# TMS320F28379D_TRIP.net
KiCad netlist of a schematic drawn in Altium Designer
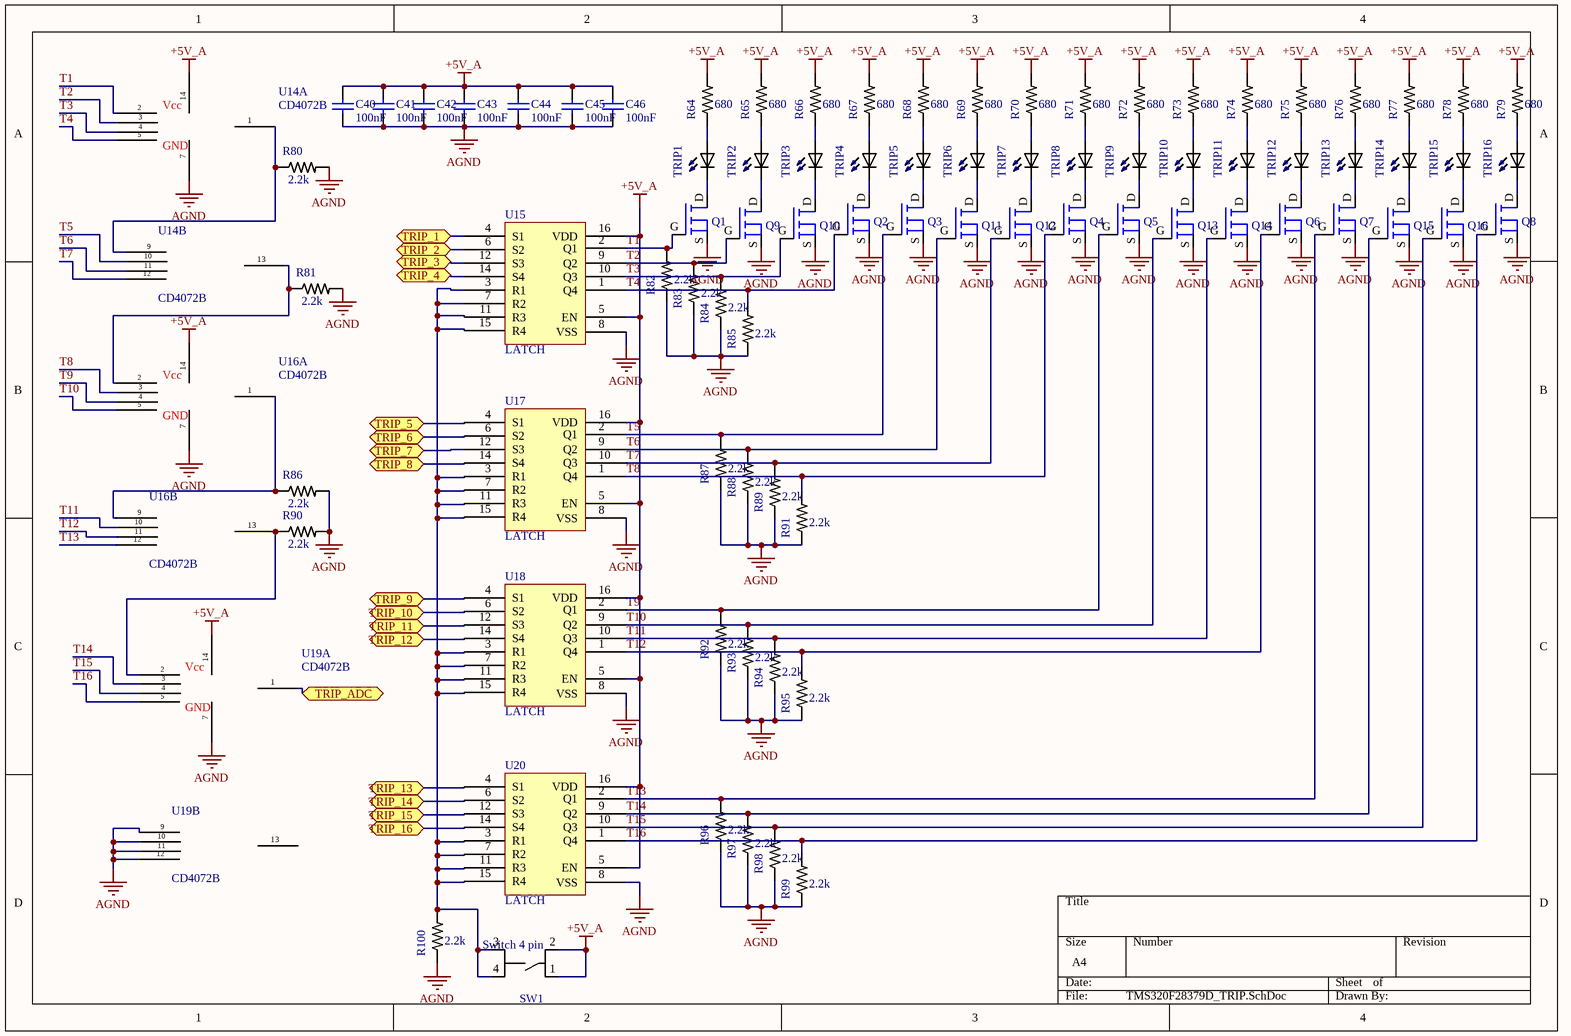
[diagram p0: TMS320F28379D_TRIP.SchDoc]

(export (version "E")
  (design (tool "Eeschema 10.0.6"))
  (components
    (comp (ref "C40")
      (value "100nF")
      (footprint "CAP 0805")
      (fields (field (name "Comment") "Cap cerámico"))
      (libsource (lib "Condensadores") (part "Cap cerámico"))
    )
    (comp (ref "C41")
      (value "100nF")
      (footprint "CAP 0805")
      (fields (field (name "Comment") "Cap cerámico"))
      (libsource (lib "Condensadores") (part "Cap cerámico"))
    )
    (comp (ref "C42")
      (value "100nF")
      (footprint "CAP 0805")
      (fields (field (name "Comment") "Cap cerámico"))
      (libsource (lib "Condensadores") (part "Cap cerámico"))
    )
    (comp (ref "C43")
      (value "100nF")
      (footprint "CAP 0805")
      (fields (field (name "Comment") "Cap cerámico"))
      (libsource (lib "Condensadores") (part "Cap cerámico"))
    )
    (comp (ref "C44")
      (value "100nF")
      (footprint "CAP 0805")
      (fields (field (name "Comment") "Cap cerámico"))
      (libsource (lib "Condensadores") (part "Cap cerámico"))
    )
    (comp (ref "C45")
      (value "100nF")
      (footprint "CAP 0805")
      (fields (field (name "Comment") "Cap cerámico"))
      (libsource (lib "Condensadores") (part "Cap cerámico"))
    )
    (comp (ref "C46")
      (value "100nF")
      (footprint "CAP 0805")
      (fields (field (name "Comment") "Cap cerámico"))
      (libsource (lib "Condensadores") (part "Cap cerámico"))
    )
    (comp (ref "Q1")
      (value "MOSFET N")
      (footprint "SOT23")
      (description "2N7002-FDICT-ND")
      (fields (field (name "MANUFACTURER PART NUMBER") "2N7002-7-F"))
      (libsource (lib "Power Semiconductors") (part "MOSFET_N"))
    )
    (comp (ref "Q2")
      (value "MOSFET N")
      (footprint "SOT23")
      (description "2N7002-FDICT-ND")
      (fields (field (name "MANUFACTURER PART NUMBER") "2N7002-7-F"))
      (libsource (lib "Power Semiconductors") (part "MOSFET_N"))
    )
    (comp (ref "Q3")
      (value "MOSFET N")
      (footprint "SOT23")
      (description "2N7002-FDICT-ND")
      (fields (field (name "MANUFACTURER PART NUMBER") "2N7002-7-F"))
      (libsource (lib "Power Semiconductors") (part "MOSFET_N"))
    )
    (comp (ref "Q4")
      (value "MOSFET N")
      (footprint "SOT23")
      (description "2N7002-FDICT-ND")
      (fields (field (name "MANUFACTURER PART NUMBER") "2N7002-7-F"))
      (libsource (lib "Power Semiconductors") (part "MOSFET_N"))
    )
    (comp (ref "Q5")
      (value "MOSFET N")
      (footprint "SOT23")
      (description "2N7002-FDICT-ND")
      (fields (field (name "MANUFACTURER PART NUMBER") "2N7002-7-F"))
      (libsource (lib "Power Semiconductors") (part "MOSFET_N"))
    )
    (comp (ref "Q6")
      (value "MOSFET N")
      (footprint "SOT23")
      (description "2N7002-FDICT-ND")
      (fields (field (name "MANUFACTURER PART NUMBER") "2N7002-7-F"))
      (libsource (lib "Power Semiconductors") (part "MOSFET_N"))
    )
    (comp (ref "Q7")
      (value "MOSFET N")
      (footprint "SOT23")
      (description "2N7002-FDICT-ND")
      (fields (field (name "MANUFACTURER PART NUMBER") "2N7002-7-F"))
      (libsource (lib "Power Semiconductors") (part "MOSFET_N"))
    )
    (comp (ref "Q8")
      (value "MOSFET N")
      (footprint "SOT23")
      (description "2N7002-FDICT-ND")
      (fields (field (name "MANUFACTURER PART NUMBER") "2N7002-7-F"))
      (libsource (lib "Power Semiconductors") (part "MOSFET_N"))
    )
    (comp (ref "Q9")
      (value "MOSFET N")
      (footprint "SOT23")
      (description "2N7002-FDICT-ND")
      (fields (field (name "MANUFACTURER PART NUMBER") "2N7002-7-F"))
      (libsource (lib "Power Semiconductors") (part "MOSFET_N"))
    )
    (comp (ref "Q10")
      (value "MOSFET N")
      (footprint "SOT23")
      (description "2N7002-FDICT-ND")
      (fields (field (name "MANUFACTURER PART NUMBER") "2N7002-7-F"))
      (libsource (lib "Power Semiconductors") (part "MOSFET_N"))
    )
    (comp (ref "Q11")
      (value "MOSFET N")
      (footprint "SOT23")
      (description "2N7002-FDICT-ND")
      (fields (field (name "MANUFACTURER PART NUMBER") "2N7002-7-F"))
      (libsource (lib "Power Semiconductors") (part "MOSFET_N"))
    )
    (comp (ref "Q12")
      (value "MOSFET N")
      (footprint "SOT23")
      (description "2N7002-FDICT-ND")
      (fields (field (name "MANUFACTURER PART NUMBER") "2N7002-7-F"))
      (libsource (lib "Power Semiconductors") (part "MOSFET_N"))
    )
    (comp (ref "Q13")
      (value "MOSFET N")
      (footprint "SOT23")
      (description "2N7002-FDICT-ND")
      (fields (field (name "MANUFACTURER PART NUMBER") "2N7002-7-F"))
      (libsource (lib "Power Semiconductors") (part "MOSFET_N"))
    )
    (comp (ref "Q14")
      (value "MOSFET N")
      (footprint "SOT23")
      (description "2N7002-FDICT-ND")
      (fields (field (name "MANUFACTURER PART NUMBER") "2N7002-7-F"))
      (libsource (lib "Power Semiconductors") (part "MOSFET_N"))
    )
    (comp (ref "Q15")
      (value "MOSFET N")
      (footprint "SOT23")
      (description "2N7002-FDICT-ND")
      (fields (field (name "MANUFACTURER PART NUMBER") "2N7002-7-F"))
      (libsource (lib "Power Semiconductors") (part "MOSFET_N"))
    )
    (comp (ref "Q16")
      (value "MOSFET N")
      (footprint "SOT23")
      (description "2N7002-FDICT-ND")
      (fields (field (name "MANUFACTURER PART NUMBER") "2N7002-7-F"))
      (libsource (lib "Power Semiconductors") (part "MOSFET_N"))
    )
    (comp (ref "R64")
      (value "680")
      (footprint "Resistor 0805")
      (description "Resistor")
      (fields (field (name "Comment") "Resistor 0805"))
      (libsource (lib "Resistencias") (part "Resistor"))
    )
    (comp (ref "R65")
      (value "680")
      (footprint "Resistor 0805")
      (description "Resistor")
      (fields (field (name "Comment") "Resistor 0805"))
      (libsource (lib "Resistencias") (part "Resistor"))
    )
    (comp (ref "R66")
      (value "680")
      (footprint "Resistor 0805")
      (description "Resistor")
      (fields (field (name "Comment") "Resistor 0805"))
      (libsource (lib "Resistencias") (part "Resistor"))
    )
    (comp (ref "R67")
      (value "680")
      (footprint "Resistor 0805")
      (description "Resistor")
      (fields (field (name "Comment") "Resistor 0805"))
      (libsource (lib "Resistencias") (part "Resistor"))
    )
    (comp (ref "R68")
      (value "680")
      (footprint "Resistor 0805")
      (description "Resistor")
      (fields (field (name "Comment") "Resistor 0805"))
      (libsource (lib "Resistencias") (part "Resistor"))
    )
    (comp (ref "R69")
      (value "680")
      (footprint "Resistor 0805")
      (description "Resistor")
      (fields (field (name "Comment") "Resistor 0805"))
      (libsource (lib "Resistencias") (part "Resistor"))
    )
    (comp (ref "R70")
      (value "680")
      (footprint "Resistor 0805")
      (description "Resistor")
      (fields (field (name "Comment") "Resistor 0805"))
      (libsource (lib "Resistencias") (part "Resistor"))
    )
    (comp (ref "R71")
      (value "680")
      (footprint "Resistor 0805")
      (description "Resistor")
      (fields (field (name "Comment") "Resistor 0805"))
      (libsource (lib "Resistencias") (part "Resistor"))
    )
    (comp (ref "R72")
      (value "680")
      (footprint "Resistor 0805")
      (description "Resistor")
      (fields (field (name "Comment") "Resistor 0805"))
      (libsource (lib "Resistencias") (part "Resistor"))
    )
    (comp (ref "R73")
      (value "680")
      (footprint "Resistor 0805")
      (description "Resistor")
      (fields (field (name "Comment") "Resistor 0805"))
      (libsource (lib "Resistencias") (part "Resistor"))
    )
    (comp (ref "R74")
      (value "680")
      (footprint "Resistor 0805")
      (description "Resistor")
      (fields (field (name "Comment") "Resistor 0805"))
      (libsource (lib "Resistencias") (part "Resistor"))
    )
    (comp (ref "R75")
      (value "680")
      (footprint "Resistor 0805")
      (description "Resistor")
      (fields (field (name "Comment") "Resistor 0805"))
      (libsource (lib "Resistencias") (part "Resistor"))
    )
    (comp (ref "R76")
      (value "680")
      (footprint "Resistor 0805")
      (description "Resistor")
      (fields (field (name "Comment") "Resistor 0805"))
      (libsource (lib "Resistencias") (part "Resistor"))
    )
    (comp (ref "R77")
      (value "680")
      (footprint "Resistor 0805")
      (description "Resistor")
      (fields (field (name "Comment") "Resistor 0805"))
      (libsource (lib "Resistencias") (part "Resistor"))
    )
    (comp (ref "R78")
      (value "680")
      (footprint "Resistor 0805")
      (description "Resistor")
      (fields (field (name "Comment") "Resistor 0805"))
      (libsource (lib "Resistencias") (part "Resistor"))
    )
    (comp (ref "R79")
      (value "680")
      (footprint "Resistor 0805")
      (description "Resistor")
      (fields (field (name "Comment") "Resistor 0805"))
      (libsource (lib "Resistencias") (part "Resistor"))
    )
    (comp (ref "R80")
      (value "2.2k")
      (footprint "Resistor 0805")
      (description "Resistor")
      (fields (field (name "Comment") "Resistor 0805"))
      (libsource (lib "Resistencias") (part "Resistor"))
    )
    (comp (ref "R81")
      (value "2.2k")
      (footprint "Resistor 0805")
      (description "Resistor")
      (fields (field (name "Comment") "Resistor 0805"))
      (libsource (lib "Resistencias") (part "Resistor"))
    )
    (comp (ref "R82")
      (value "2.2k")
      (footprint "Resistor 0805")
      (description "Resistor")
      (fields (field (name "Comment") "Resistor 0805"))
      (libsource (lib "Resistencias") (part "Resistor"))
    )
    (comp (ref "R83")
      (value "2.2k")
      (footprint "Resistor 0805")
      (description "Resistor")
      (fields (field (name "Comment") "Resistor 0805"))
      (libsource (lib "Resistencias") (part "Resistor"))
    )
    (comp (ref "R84")
      (value "2.2k")
      (footprint "Resistor 0805")
      (description "Resistor")
      (fields (field (name "Comment") "Resistor 0805"))
      (libsource (lib "Resistencias") (part "Resistor"))
    )
    (comp (ref "R85")
      (value "2.2k")
      (footprint "Resistor 0805")
      (description "Resistor")
      (fields (field (name "Comment") "Resistor 0805"))
      (libsource (lib "Resistencias") (part "Resistor"))
    )
    (comp (ref "R86")
      (value "2.2k")
      (footprint "Resistor 0805")
      (description "Resistor")
      (fields (field (name "Comment") "Resistor 0805"))
      (libsource (lib "Resistencias") (part "Resistor"))
    )
    (comp (ref "R87")
      (value "2.2k")
      (footprint "Resistor 0805")
      (description "Resistor")
      (fields (field (name "Comment") "Resistor 0805"))
      (libsource (lib "Resistencias") (part "Resistor"))
    )
    (comp (ref "R88")
      (value "2.2k")
      (footprint "Resistor 0805")
      (description "Resistor")
      (fields (field (name "Comment") "Resistor 0805"))
      (libsource (lib "Resistencias") (part "Resistor"))
    )
    (comp (ref "R89")
      (value "2.2k")
      (footprint "Resistor 0805")
      (description "Resistor")
      (fields (field (name "Comment") "Resistor 0805"))
      (libsource (lib "Resistencias") (part "Resistor"))
    )
    (comp (ref "R90")
      (value "2.2k")
      (footprint "Resistor 0805")
      (description "Resistor")
      (fields (field (name "Comment") "Resistor 0805"))
      (libsource (lib "Resistencias") (part "Resistor"))
    )
    (comp (ref "R91")
      (value "2.2k")
      (footprint "Resistor 0805")
      (description "Resistor")
      (fields (field (name "Comment") "Resistor 0805"))
      (libsource (lib "Resistencias") (part "Resistor"))
    )
    (comp (ref "R92")
      (value "2.2k")
      (footprint "Resistor 0805")
      (description "Resistor")
      (fields (field (name "Comment") "Resistor 0805"))
      (libsource (lib "Resistencias") (part "Resistor"))
    )
    (comp (ref "R93")
      (value "2.2k")
      (footprint "Resistor 0805")
      (description "Resistor")
      (fields (field (name "Comment") "Resistor 0805"))
      (libsource (lib "Resistencias") (part "Resistor"))
    )
    (comp (ref "R94")
      (value "2.2k")
      (footprint "Resistor 0805")
      (description "Resistor")
      (fields (field (name "Comment") "Resistor 0805"))
      (libsource (lib "Resistencias") (part "Resistor"))
    )
    (comp (ref "R95")
      (value "2.2k")
      (footprint "Resistor 0805")
      (description "Resistor")
      (fields (field (name "Comment") "Resistor 0805"))
      (libsource (lib "Resistencias") (part "Resistor"))
    )
    (comp (ref "R96")
      (value "2.2k")
      (footprint "Resistor 0805")
      (description "Resistor")
      (fields (field (name "Comment") "Resistor 0805"))
      (libsource (lib "Resistencias") (part "Resistor"))
    )
    (comp (ref "R97")
      (value "2.2k")
      (footprint "Resistor 0805")
      (description "Resistor")
      (fields (field (name "Comment") "Resistor 0805"))
      (libsource (lib "Resistencias") (part "Resistor"))
    )
    (comp (ref "R98")
      (value "2.2k")
      (footprint "Resistor 0805")
      (description "Resistor")
      (fields (field (name "Comment") "Resistor 0805"))
      (libsource (lib "Resistencias") (part "Resistor"))
    )
    (comp (ref "R99")
      (value "2.2k")
      (footprint "Resistor 0805")
      (description "Resistor")
      (fields (field (name "Comment") "Resistor 0805"))
      (libsource (lib "Resistencias") (part "Resistor"))
    )
    (comp (ref "R100")
      (value "2.2k")
      (footprint "Resistor 0805")
      (description "Resistor")
      (fields (field (name "Comment") "Resistor 0805"))
      (libsource (lib "Resistencias") (part "Resistor"))
    )
    (comp (ref "SW1")
      (value "Switch 4 pin")
      (footprint "Switch 4 pin")
      (fields
        (field (name "DIGI-KEY PART NUMBER") "CKN10899-ND")
        (field (name "MANUFACTURER PART NUMBER") "PTS645SM43-2 LFS")
      )
      (libsource (lib "Otros") (part "Switch 4 pin"))
    )
    (comp (ref "TRIP1")
      (value "LED")
      (footprint "LED_0805")
      (description "Led")
      (fields
        (field (name "DIGI-KEY PART NUMBER") "732-4984-1-ND")
        (field (name "MANUFACTURER PART NUMBER") "150080RS75000")
      )
      (libsource (lib "Fibras Opticas") (part "LED"))
    )
    (comp (ref "TRIP2")
      (value "LED")
      (footprint "LED_0805")
      (description "Led")
      (fields
        (field (name "DIGI-KEY PART NUMBER") "732-4984-1-ND")
        (field (name "MANUFACTURER PART NUMBER") "150080RS75000")
      )
      (libsource (lib "Fibras Opticas") (part "LED"))
    )
    (comp (ref "TRIP3")
      (value "LED")
      (footprint "LED_0805")
      (description "Led")
      (fields
        (field (name "DIGI-KEY PART NUMBER") "732-4984-1-ND")
        (field (name "MANUFACTURER PART NUMBER") "150080RS75000")
      )
      (libsource (lib "Fibras Opticas") (part "LED"))
    )
    (comp (ref "TRIP4")
      (value "LED")
      (footprint "LED_0805")
      (description "Led")
      (fields
        (field (name "DIGI-KEY PART NUMBER") "732-4984-1-ND")
        (field (name "MANUFACTURER PART NUMBER") "150080RS75000")
      )
      (libsource (lib "Fibras Opticas") (part "LED"))
    )
    (comp (ref "TRIP5")
      (value "LED")
      (footprint "LED_0805")
      (description "Led")
      (fields
        (field (name "DIGI-KEY PART NUMBER") "732-4984-1-ND")
        (field (name "MANUFACTURER PART NUMBER") "150080RS75000")
      )
      (libsource (lib "Fibras Opticas") (part "LED"))
    )
    (comp (ref "TRIP6")
      (value "LED")
      (footprint "LED_0805")
      (description "Led")
      (fields
        (field (name "DIGI-KEY PART NUMBER") "732-4984-1-ND")
        (field (name "MANUFACTURER PART NUMBER") "150080RS75000")
      )
      (libsource (lib "Fibras Opticas") (part "LED"))
    )
    (comp (ref "TRIP7")
      (value "LED")
      (footprint "LED_0805")
      (description "Led")
      (fields
        (field (name "DIGI-KEY PART NUMBER") "732-4984-1-ND")
        (field (name "MANUFACTURER PART NUMBER") "150080RS75000")
      )
      (libsource (lib "Fibras Opticas") (part "LED"))
    )
    (comp (ref "TRIP8")
      (value "LED")
      (footprint "LED_0805")
      (description "Led")
      (fields
        (field (name "DIGI-KEY PART NUMBER") "732-4984-1-ND")
        (field (name "MANUFACTURER PART NUMBER") "150080RS75000")
      )
      (libsource (lib "Fibras Opticas") (part "LED"))
    )
    (comp (ref "TRIP9")
      (value "LED")
      (footprint "LED_0805")
      (description "Led")
      (fields
        (field (name "DIGI-KEY PART NUMBER") "732-4984-1-ND")
        (field (name "MANUFACTURER PART NUMBER") "150080RS75000")
      )
      (libsource (lib "Fibras Opticas") (part "LED"))
    )
    (comp (ref "TRIP10")
      (value "LED")
      (footprint "LED_0805")
      (description "Led")
      (fields
        (field (name "DIGI-KEY PART NUMBER") "732-4984-1-ND")
        (field (name "MANUFACTURER PART NUMBER") "150080RS75000")
      )
      (libsource (lib "Fibras Opticas") (part "LED"))
    )
    (comp (ref "TRIP11")
      (value "LED")
      (footprint "LED_0805")
      (description "Led")
      (fields
        (field (name "DIGI-KEY PART NUMBER") "732-4984-1-ND")
        (field (name "MANUFACTURER PART NUMBER") "150080RS75000")
      )
      (libsource (lib "Fibras Opticas") (part "LED"))
    )
    (comp (ref "TRIP12")
      (value "LED")
      (footprint "LED_0805")
      (description "Led")
      (fields
        (field (name "DIGI-KEY PART NUMBER") "732-4984-1-ND")
        (field (name "MANUFACTURER PART NUMBER") "150080RS75000")
      )
      (libsource (lib "Fibras Opticas") (part "LED"))
    )
    (comp (ref "TRIP13")
      (value "LED")
      (footprint "LED_0805")
      (description "Led")
      (fields
        (field (name "DIGI-KEY PART NUMBER") "732-4984-1-ND")
        (field (name "MANUFACTURER PART NUMBER") "150080RS75000")
      )
      (libsource (lib "Fibras Opticas") (part "LED"))
    )
    (comp (ref "TRIP14")
      (value "LED")
      (footprint "LED_0805")
      (description "Led")
      (fields
        (field (name "DIGI-KEY PART NUMBER") "732-4984-1-ND")
        (field (name "MANUFACTURER PART NUMBER") "150080RS75000")
      )
      (libsource (lib "Fibras Opticas") (part "LED"))
    )
    (comp (ref "TRIP15")
      (value "LED")
      (footprint "LED_0805")
      (description "Led")
      (fields
        (field (name "DIGI-KEY PART NUMBER") "732-4984-1-ND")
        (field (name "MANUFACTURER PART NUMBER") "150080RS75000")
      )
      (libsource (lib "Fibras Opticas") (part "LED"))
    )
    (comp (ref "TRIP16")
      (value "LED")
      (footprint "LED_0805")
      (description "Led")
      (fields
        (field (name "DIGI-KEY PART NUMBER") "732-4984-1-ND")
        (field (name "MANUFACTURER PART NUMBER") "150080RS75000")
      )
      (libsource (lib "Fibras Opticas") (part "LED"))
    )
    (comp (ref "U14")
      (value "CD4072B")
      (footprint "14-TSSOP")
      (description "2 OR GATE 4 INPUT")
      (fields
        (field (name "DIGI-KEY PART NUMBER") "296-32907-5-ND")
        (field (name "MANUFACTURER PART NUMBER") "CD4072BPW")
      )
      (libsource (lib "Circuitos integrados") (part "CD4072B"))
    )
    (comp (ref "U15")
      (value "LATCH")
      (footprint "16-SOIC")
      (description "IC R/S LATCH 3-STATE QUAD 16SOIC")
      (fields
        (field (name "DIGI-KEY PART NUMBER") "1727-1799-1-ND")
        (field (name "MANUFACTURER PART NUMBER") "HEF4043BT,653")
      )
      (libsource (lib "Circuitos integrados") (part "HEF4043"))
    )
    (comp (ref "U16")
      (value "CD4072B")
      (footprint "14-TSSOP")
      (description "2 OR GATE 4 INPUT")
      (fields
        (field (name "DIGI-KEY PART NUMBER") "296-32907-5-ND")
        (field (name "MANUFACTURER PART NUMBER") "CD4072BPW")
      )
      (libsource (lib "Circuitos integrados") (part "CD4072B"))
    )
    (comp (ref "U17")
      (value "LATCH")
      (footprint "16-SOIC")
      (description "IC R/S LATCH 3-STATE QUAD 16SOIC")
      (fields
        (field (name "DIGI-KEY PART NUMBER") "1727-1799-1-ND")
        (field (name "MANUFACTURER PART NUMBER") "HEF4043BT,653")
      )
      (libsource (lib "Circuitos integrados") (part "HEF4043"))
    )
    (comp (ref "U18")
      (value "LATCH")
      (footprint "16-SOIC")
      (description "IC R/S LATCH 3-STATE QUAD 16SOIC")
      (fields
        (field (name "DIGI-KEY PART NUMBER") "1727-1799-1-ND")
        (field (name "MANUFACTURER PART NUMBER") "HEF4043BT,653")
      )
      (libsource (lib "Circuitos integrados") (part "HEF4043"))
    )
    (comp (ref "U19")
      (value "CD4072B")
      (footprint "14-TSSOP")
      (description "2 OR GATE 4 INPUT")
      (fields
        (field (name "DIGI-KEY PART NUMBER") "296-32907-5-ND")
        (field (name "MANUFACTURER PART NUMBER") "CD4072BPW")
      )
      (libsource (lib "Circuitos integrados") (part "CD4072B"))
    )
    (comp (ref "U20")
      (value "LATCH")
      (footprint "16-SOIC")
      (description "IC R/S LATCH 3-STATE QUAD 16SOIC")
      (fields
        (field (name "DIGI-KEY PART NUMBER") "1727-1799-1-ND")
        (field (name "MANUFACTURER PART NUMBER") "HEF4043BT,653")
      )
      (libsource (lib "Circuitos integrados") (part "HEF4043"))
    )
  )
  (nets
    (net (code "1") (name "+5V_A") (class "Default")
      (node (ref "C40") (pin "1") (pinfunction "1_1") (pintype "passive"))
      (node (ref "C41") (pin "1") (pinfunction "1_1") (pintype "passive"))
      (node (ref "C42") (pin "1") (pinfunction "1_1") (pintype "passive"))
      (node (ref "C43") (pin "1") (pinfunction "1_1") (pintype "passive"))
      (node (ref "C44") (pin "1") (pinfunction "1_1") (pintype "passive"))
      (node (ref "C45") (pin "1") (pinfunction "1_1") (pintype "passive"))
      (node (ref "C46") (pin "1") (pinfunction "1_1") (pintype "passive"))
      (node (ref "R64") (pin "2") (pinfunction "2_2") (pintype "passive"))
      (node (ref "R65") (pin "2") (pinfunction "2_2") (pintype "passive"))
      (node (ref "R66") (pin "2") (pinfunction "2_2") (pintype "passive"))
      (node (ref "R67") (pin "2") (pinfunction "2_2") (pintype "passive"))
      (node (ref "R68") (pin "2") (pinfunction "2_2") (pintype "passive"))
      (node (ref "R69") (pin "2") (pinfunction "2_2") (pintype "passive"))
      (node (ref "R70") (pin "2") (pinfunction "2_2") (pintype "passive"))
      (node (ref "R71") (pin "2") (pinfunction "2_2") (pintype "passive"))
      (node (ref "R72") (pin "2") (pinfunction "2_2") (pintype "passive"))
      (node (ref "R73") (pin "2") (pinfunction "2_2") (pintype "passive"))
      (node (ref "R74") (pin "2") (pinfunction "2_2") (pintype "passive"))
      (node (ref "R75") (pin "2") (pinfunction "2_2") (pintype "passive"))
      (node (ref "R76") (pin "2") (pinfunction "2_2") (pintype "passive"))
      (node (ref "R77") (pin "2") (pinfunction "2_2") (pintype "passive"))
      (node (ref "R78") (pin "2") (pinfunction "2_2") (pintype "passive"))
      (node (ref "R79") (pin "2") (pinfunction "2_2") (pintype "passive"))
      (node (ref "SW1") (pin "1") (pinfunction "1_1") (pintype "passive"))
      (node (ref "SW1") (pin "2") (pinfunction "2_2") (pintype "passive"))
      (node (ref "U14") (pin "14") (pinfunction "14_14") (pintype "passive"))
      (node (ref "U15") (pin "16") (pinfunction "VDD_16") (pintype "passive"))
      (node (ref "U15") (pin "5") (pinfunction "EN_5") (pintype "passive"))
      (node (ref "U16") (pin "14") (pinfunction "14_14") (pintype "passive"))
      (node (ref "U17") (pin "16") (pinfunction "VDD_16") (pintype "passive"))
      (node (ref "U17") (pin "5") (pinfunction "EN_5") (pintype "passive"))
      (node (ref "U18") (pin "16") (pinfunction "VDD_16") (pintype "passive"))
      (node (ref "U18") (pin "5") (pinfunction "EN_5") (pintype "passive"))
      (node (ref "U19") (pin "14") (pinfunction "14_14") (pintype "passive"))
      (node (ref "U20") (pin "16") (pinfunction "VDD_16") (pintype "passive"))
      (node (ref "U20") (pin "5") (pinfunction "EN_5") (pintype "passive"))
    )
    (net (code "2") (name "/T1") (class "Default")
      (node (ref "Q1") (pin "G") (pinfunction "G_G") (pintype "passive"))
      (node (ref "R82") (pin "2") (pinfunction "2_2") (pintype "passive"))
      (node (ref "U14") (pin "2") (pinfunction "2_2") (pintype "passive"))
      (node (ref "U15") (pin "2") (pinfunction "Q1_2") (pintype "passive"))
    )
    (net (code "3") (name "/T2") (class "Default")
      (node (ref "Q9") (pin "G") (pinfunction "G_G") (pintype "passive"))
      (node (ref "R83") (pin "2") (pinfunction "2_2") (pintype "passive"))
      (node (ref "U14") (pin "3") (pinfunction "3_3") (pintype "passive"))
      (node (ref "U15") (pin "9") (pinfunction "Q2_9") (pintype "passive"))
    )
    (net (code "4") (name "/T3") (class "Default")
      (node (ref "Q10") (pin "G") (pinfunction "G_G") (pintype "passive"))
      (node (ref "R84") (pin "2") (pinfunction "2_2") (pintype "passive"))
      (node (ref "U14") (pin "4") (pinfunction "4_4") (pintype "passive"))
      (node (ref "U15") (pin "10") (pinfunction "Q3_10") (pintype "passive"))
    )
    (net (code "5") (name "/T4") (class "Default")
      (node (ref "Q2") (pin "G") (pinfunction "G_G") (pintype "passive"))
      (node (ref "R85") (pin "2") (pinfunction "2_2") (pintype "passive"))
      (node (ref "U14") (pin "5") (pinfunction "5_5") (pintype "passive"))
      (node (ref "U15") (pin "1") (pinfunction "Q4_1") (pintype "passive"))
    )
    (net (code "6") (name "/T5") (class "Default")
      (node (ref "Q3") (pin "G") (pinfunction "G_G") (pintype "passive"))
      (node (ref "R87") (pin "2") (pinfunction "2_2") (pintype "passive"))
      (node (ref "U14") (pin "10") (pinfunction "10_10") (pintype "passive"))
      (node (ref "U17") (pin "2") (pinfunction "Q1_2") (pintype "passive"))
    )
    (net (code "7") (name "/T6") (class "Default")
      (node (ref "Q11") (pin "G") (pinfunction "G_G") (pintype "passive"))
      (node (ref "R88") (pin "2") (pinfunction "2_2") (pintype "passive"))
      (node (ref "U14") (pin "11") (pinfunction "11_11") (pintype "passive"))
      (node (ref "U17") (pin "9") (pinfunction "Q2_9") (pintype "passive"))
    )
    (net (code "8") (name "/T7") (class "Default")
      (node (ref "Q12") (pin "G") (pinfunction "G_G") (pintype "passive"))
      (node (ref "R89") (pin "2") (pinfunction "2_2") (pintype "passive"))
      (node (ref "U14") (pin "12") (pinfunction "12_12") (pintype "passive"))
      (node (ref "U17") (pin "10") (pinfunction "Q3_10") (pintype "passive"))
    )
    (net (code "9") (name "/T8") (class "Default")
      (node (ref "Q4") (pin "G") (pinfunction "G_G") (pintype "passive"))
      (node (ref "R91") (pin "2") (pinfunction "2_2") (pintype "passive"))
      (node (ref "U16") (pin "3") (pinfunction "3_3") (pintype "passive"))
      (node (ref "U17") (pin "1") (pinfunction "Q4_1") (pintype "passive"))
    )
    (net (code "10") (name "/T9") (class "Default")
      (node (ref "Q5") (pin "G") (pinfunction "G_G") (pintype "passive"))
      (node (ref "R92") (pin "2") (pinfunction "2_2") (pintype "passive"))
      (node (ref "U16") (pin "4") (pinfunction "4_4") (pintype "passive"))
      (node (ref "U18") (pin "2") (pinfunction "Q1_2") (pintype "passive"))
    )
    (net (code "11") (name "/T10") (class "Default")
      (node (ref "Q13") (pin "G") (pinfunction "G_G") (pintype "passive"))
      (node (ref "R93") (pin "2") (pinfunction "2_2") (pintype "passive"))
      (node (ref "U16") (pin "5") (pinfunction "5_5") (pintype "passive"))
      (node (ref "U18") (pin "9") (pinfunction "Q2_9") (pintype "passive"))
    )
    (net (code "12") (name "/T11") (class "Default")
      (node (ref "Q14") (pin "G") (pinfunction "G_G") (pintype "passive"))
      (node (ref "R94") (pin "2") (pinfunction "2_2") (pintype "passive"))
      (node (ref "U16") (pin "10") (pinfunction "10_10") (pintype "passive"))
      (node (ref "U18") (pin "10") (pinfunction "Q3_10") (pintype "passive"))
    )
    (net (code "13") (name "/T12") (class "Default")
      (node (ref "Q6") (pin "G") (pinfunction "G_G") (pintype "passive"))
      (node (ref "R95") (pin "2") (pinfunction "2_2") (pintype "passive"))
      (node (ref "U16") (pin "11") (pinfunction "11_11") (pintype "passive"))
      (node (ref "U18") (pin "1") (pinfunction "Q4_1") (pintype "passive"))
    )
    (net (code "14") (name "/T13") (class "Default")
      (node (ref "Q7") (pin "G") (pinfunction "G_G") (pintype "passive"))
      (node (ref "R96") (pin "2") (pinfunction "2_2") (pintype "passive"))
      (node (ref "U16") (pin "12") (pinfunction "12_12") (pintype "passive"))
      (node (ref "U20") (pin "2") (pinfunction "Q1_2") (pintype "passive"))
    )
    (net (code "15") (name "/T14") (class "Default")
      (node (ref "Q15") (pin "G") (pinfunction "G_G") (pintype "passive"))
      (node (ref "R97") (pin "2") (pinfunction "2_2") (pintype "passive"))
      (node (ref "U19") (pin "3") (pinfunction "3_3") (pintype "passive"))
      (node (ref "U20") (pin "9") (pinfunction "Q2_9") (pintype "passive"))
    )
    (net (code "16") (name "/T15") (class "Default")
      (node (ref "Q16") (pin "G") (pinfunction "G_G") (pintype "passive"))
      (node (ref "R98") (pin "2") (pinfunction "2_2") (pintype "passive"))
      (node (ref "U19") (pin "4") (pinfunction "4_4") (pintype "passive"))
      (node (ref "U20") (pin "10") (pinfunction "Q3_10") (pintype "passive"))
    )
    (net (code "17") (name "/T16") (class "Default")
      (node (ref "Q8") (pin "G") (pinfunction "G_G") (pintype "passive"))
      (node (ref "R99") (pin "2") (pinfunction "2_2") (pintype "passive"))
      (node (ref "U19") (pin "5") (pinfunction "5_5") (pintype "passive"))
      (node (ref "U20") (pin "1") (pinfunction "Q4_1") (pintype "passive"))
    )
    (net (code "18") (name "/TRIP_1") (class "Default")
      (node (ref "U15") (pin "4") (pinfunction "S1_4") (pintype "passive"))
    )
    (net (code "19") (name "/TRIP_2") (class "Default")
      (node (ref "U15") (pin "6") (pinfunction "S2_6") (pintype "passive"))
    )
    (net (code "20") (name "/TRIP_3") (class "Default")
      (node (ref "U15") (pin "12") (pinfunction "S3_12") (pintype "passive"))
    )
    (net (code "21") (name "/TRIP_4") (class "Default")
      (node (ref "U15") (pin "14") (pinfunction "S4_14") (pintype "passive"))
    )
    (net (code "22") (name "/TRIP_5") (class "Default")
      (node (ref "U17") (pin "4") (pinfunction "S1_4") (pintype "passive"))
    )
    (net (code "23") (name "/TRIP_6") (class "Default")
      (node (ref "U17") (pin "6") (pinfunction "S2_6") (pintype "passive"))
    )
    (net (code "24") (name "/TRIP_7") (class "Default")
      (node (ref "U17") (pin "12") (pinfunction "S3_12") (pintype "passive"))
    )
    (net (code "25") (name "/TRIP_8") (class "Default")
      (node (ref "U17") (pin "14") (pinfunction "S4_14") (pintype "passive"))
    )
    (net (code "26") (name "/TRIP_9") (class "Default")
      (node (ref "U18") (pin "4") (pinfunction "S1_4") (pintype "passive"))
    )
    (net (code "27") (name "/TRIP_10") (class "Default")
      (node (ref "U18") (pin "6") (pinfunction "S2_6") (pintype "passive"))
    )
    (net (code "28") (name "/TRIP_11") (class "Default")
      (node (ref "U18") (pin "12") (pinfunction "S3_12") (pintype "passive"))
    )
    (net (code "29") (name "/TRIP_12") (class "Default")
      (node (ref "U18") (pin "14") (pinfunction "S4_14") (pintype "passive"))
    )
    (net (code "30") (name "/TRIP_13") (class "Default")
      (node (ref "U20") (pin "4") (pinfunction "S1_4") (pintype "passive"))
    )
    (net (code "31") (name "/TRIP_14") (class "Default")
      (node (ref "U20") (pin "6") (pinfunction "S2_6") (pintype "passive"))
    )
    (net (code "32") (name "/TRIP_15") (class "Default")
      (node (ref "U20") (pin "12") (pinfunction "S3_12") (pintype "passive"))
    )
    (net (code "33") (name "/TRIP_16") (class "Default")
      (node (ref "U20") (pin "14") (pinfunction "S4_14") (pintype "passive"))
    )
    (net (code "34") (name "/TRIP_ADC") (class "Default")
      (node (ref "U19") (pin "1") (pinfunction "1_1") (pintype "passive"))
    )
    (net (code "35") (name "AGND") (class "Default")
      (node (ref "C40") (pin "2") (pinfunction "2_2") (pintype "passive"))
      (node (ref "C41") (pin "2") (pinfunction "2_2") (pintype "passive"))
      (node (ref "C42") (pin "2") (pinfunction "2_2") (pintype "passive"))
      (node (ref "C43") (pin "2") (pinfunction "2_2") (pintype "passive"))
      (node (ref "C44") (pin "2") (pinfunction "2_2") (pintype "passive"))
      (node (ref "C45") (pin "2") (pinfunction "2_2") (pintype "passive"))
      (node (ref "C46") (pin "2") (pinfunction "2_2") (pintype "passive"))
      (node (ref "Q1") (pin "S") (pinfunction "S_S") (pintype "passive"))
      (node (ref "Q10") (pin "S") (pinfunction "S_S") (pintype "passive"))
      (node (ref "Q11") (pin "S") (pinfunction "S_S") (pintype "passive"))
      (node (ref "Q12") (pin "S") (pinfunction "S_S") (pintype "passive"))
      (node (ref "Q13") (pin "S") (pinfunction "S_S") (pintype "passive"))
      (node (ref "Q14") (pin "S") (pinfunction "S_S") (pintype "passive"))
      (node (ref "Q15") (pin "S") (pinfunction "S_S") (pintype "passive"))
      (node (ref "Q16") (pin "S") (pinfunction "S_S") (pintype "passive"))
      (node (ref "Q2") (pin "S") (pinfunction "S_S") (pintype "passive"))
      (node (ref "Q3") (pin "S") (pinfunction "S_S") (pintype "passive"))
      (node (ref "Q4") (pin "S") (pinfunction "S_S") (pintype "passive"))
      (node (ref "Q5") (pin "S") (pinfunction "S_S") (pintype "passive"))
      (node (ref "Q6") (pin "S") (pinfunction "S_S") (pintype "passive"))
      (node (ref "Q7") (pin "S") (pinfunction "S_S") (pintype "passive"))
      (node (ref "Q8") (pin "S") (pinfunction "S_S") (pintype "passive"))
      (node (ref "Q9") (pin "S") (pinfunction "S_S") (pintype "passive"))
      (node (ref "R100") (pin "1") (pinfunction "1_1") (pintype "passive"))
      (node (ref "R80") (pin "2") (pinfunction "2_2") (pintype "passive"))
      (node (ref "R81") (pin "2") (pinfunction "2_2") (pintype "passive"))
      (node (ref "R82") (pin "1") (pinfunction "1_1") (pintype "passive"))
      (node (ref "R83") (pin "1") (pinfunction "1_1") (pintype "passive"))
      (node (ref "R84") (pin "1") (pinfunction "1_1") (pintype "passive"))
      (node (ref "R85") (pin "1") (pinfunction "1_1") (pintype "passive"))
      (node (ref "R86") (pin "2") (pinfunction "2_2") (pintype "passive"))
      (node (ref "R87") (pin "1") (pinfunction "1_1") (pintype "passive"))
      (node (ref "R88") (pin "1") (pinfunction "1_1") (pintype "passive"))
      (node (ref "R89") (pin "1") (pinfunction "1_1") (pintype "passive"))
      (node (ref "R90") (pin "2") (pinfunction "2_2") (pintype "passive"))
      (node (ref "R91") (pin "1") (pinfunction "1_1") (pintype "passive"))
      (node (ref "R92") (pin "1") (pinfunction "1_1") (pintype "passive"))
      (node (ref "R93") (pin "1") (pinfunction "1_1") (pintype "passive"))
      (node (ref "R94") (pin "1") (pinfunction "1_1") (pintype "passive"))
      (node (ref "R95") (pin "1") (pinfunction "1_1") (pintype "passive"))
      (node (ref "R96") (pin "1") (pinfunction "1_1") (pintype "passive"))
      (node (ref "R97") (pin "1") (pinfunction "1_1") (pintype "passive"))
      (node (ref "R98") (pin "1") (pinfunction "1_1") (pintype "passive"))
      (node (ref "R99") (pin "1") (pinfunction "1_1") (pintype "passive"))
      (node (ref "U14") (pin "7") (pinfunction "7_7") (pintype "passive"))
      (node (ref "U15") (pin "8") (pinfunction "VSS_8") (pintype "passive"))
      (node (ref "U16") (pin "7") (pinfunction "7_7") (pintype "passive"))
      (node (ref "U17") (pin "8") (pinfunction "VSS_8") (pintype "passive"))
      (node (ref "U18") (pin "8") (pinfunction "VSS_8") (pintype "passive"))
      (node (ref "U19") (pin "10") (pinfunction "10_10") (pintype "passive"))
      (node (ref "U19") (pin "11") (pinfunction "11_11") (pintype "passive"))
      (node (ref "U19") (pin "12") (pinfunction "12_12") (pintype "passive"))
      (node (ref "U19") (pin "7") (pinfunction "7_7") (pintype "passive"))
      (node (ref "U19") (pin "9") (pinfunction "9_9") (pintype "passive"))
      (node (ref "U20") (pin "8") (pinfunction "VSS_8") (pintype "passive"))
    )
    (net (code "36") (name "Net-(R80-Pad1)") (class "Default")
      (node (ref "R80") (pin "1") (pinfunction "1_1") (pintype "passive"))
      (node (ref "U14") (pin "1") (pinfunction "1_1") (pintype "passive"))
      (node (ref "U14") (pin "9") (pinfunction "9_9") (pintype "passive"))
    )
    (net (code "37") (name "Net-(R81-Pad1)") (class "Default")
      (node (ref "R81") (pin "1") (pinfunction "1_1") (pintype "passive"))
      (node (ref "U14") (pin "13") (pinfunction "13_13") (pintype "passive"))
      (node (ref "U16") (pin "2") (pinfunction "2_2") (pintype "passive"))
    )
    (net (code "38") (name "Net-(R86-Pad1)") (class "Default")
      (node (ref "R86") (pin "1") (pinfunction "1_1") (pintype "passive"))
      (node (ref "U16") (pin "1") (pinfunction "1_1") (pintype "passive"))
      (node (ref "U16") (pin "9") (pinfunction "9_9") (pintype "passive"))
    )
    (net (code "39") (name "Net-(R90-Pad1)") (class "Default")
      (node (ref "R90") (pin "1") (pinfunction "1_1") (pintype "passive"))
      (node (ref "U16") (pin "13") (pinfunction "13_13") (pintype "passive"))
      (node (ref "U19") (pin "2") (pinfunction "2_2") (pintype "passive"))
    )
    (net (code "40") (name "Net-(TRIP1-NEG)") (class "Default")
      (node (ref "Q1") (pin "D") (pinfunction "D_D") (pintype "passive"))
      (node (ref "TRIP1") (pin "1") (pinfunction "NEG_1") (pintype "passive"))
    )
    (net (code "41") (name "Net-(TRIP1-POS)") (class "Default")
      (node (ref "R64") (pin "1") (pinfunction "1_1") (pintype "passive"))
      (node (ref "TRIP1") (pin "2") (pinfunction "POS_2") (pintype "passive"))
    )
    (net (code "42") (name "Net-(TRIP2-NEG)") (class "Default")
      (node (ref "Q9") (pin "D") (pinfunction "D_D") (pintype "passive"))
      (node (ref "TRIP2") (pin "1") (pinfunction "NEG_1") (pintype "passive"))
    )
    (net (code "43") (name "Net-(TRIP2-POS)") (class "Default")
      (node (ref "R65") (pin "1") (pinfunction "1_1") (pintype "passive"))
      (node (ref "TRIP2") (pin "2") (pinfunction "POS_2") (pintype "passive"))
    )
    (net (code "44") (name "Net-(TRIP3-NEG)") (class "Default")
      (node (ref "Q10") (pin "D") (pinfunction "D_D") (pintype "passive"))
      (node (ref "TRIP3") (pin "1") (pinfunction "NEG_1") (pintype "passive"))
    )
    (net (code "45") (name "Net-(TRIP3-POS)") (class "Default")
      (node (ref "R66") (pin "1") (pinfunction "1_1") (pintype "passive"))
      (node (ref "TRIP3") (pin "2") (pinfunction "POS_2") (pintype "passive"))
    )
    (net (code "46") (name "Net-(TRIP4-NEG)") (class "Default")
      (node (ref "Q2") (pin "D") (pinfunction "D_D") (pintype "passive"))
      (node (ref "TRIP4") (pin "1") (pinfunction "NEG_1") (pintype "passive"))
    )
    (net (code "47") (name "Net-(TRIP4-POS)") (class "Default")
      (node (ref "R67") (pin "1") (pinfunction "1_1") (pintype "passive"))
      (node (ref "TRIP4") (pin "2") (pinfunction "POS_2") (pintype "passive"))
    )
    (net (code "48") (name "Net-(TRIP5-NEG)") (class "Default")
      (node (ref "Q3") (pin "D") (pinfunction "D_D") (pintype "passive"))
      (node (ref "TRIP5") (pin "1") (pinfunction "NEG_1") (pintype "passive"))
    )
    (net (code "49") (name "Net-(TRIP5-POS)") (class "Default")
      (node (ref "R68") (pin "1") (pinfunction "1_1") (pintype "passive"))
      (node (ref "TRIP5") (pin "2") (pinfunction "POS_2") (pintype "passive"))
    )
    (net (code "50") (name "Net-(TRIP6-NEG)") (class "Default")
      (node (ref "Q11") (pin "D") (pinfunction "D_D") (pintype "passive"))
      (node (ref "TRIP6") (pin "1") (pinfunction "NEG_1") (pintype "passive"))
    )
    (net (code "51") (name "Net-(TRIP6-POS)") (class "Default")
      (node (ref "R69") (pin "1") (pinfunction "1_1") (pintype "passive"))
      (node (ref "TRIP6") (pin "2") (pinfunction "POS_2") (pintype "passive"))
    )
    (net (code "52") (name "Net-(TRIP7-NEG)") (class "Default")
      (node (ref "Q12") (pin "D") (pinfunction "D_D") (pintype "passive"))
      (node (ref "TRIP7") (pin "1") (pinfunction "NEG_1") (pintype "passive"))
    )
    (net (code "53") (name "Net-(TRIP7-POS)") (class "Default")
      (node (ref "R70") (pin "1") (pinfunction "1_1") (pintype "passive"))
      (node (ref "TRIP7") (pin "2") (pinfunction "POS_2") (pintype "passive"))
    )
    (net (code "54") (name "Net-(TRIP8-NEG)") (class "Default")
      (node (ref "Q4") (pin "D") (pinfunction "D_D") (pintype "passive"))
      (node (ref "TRIP8") (pin "1") (pinfunction "NEG_1") (pintype "passive"))
    )
    (net (code "55") (name "Net-(TRIP8-POS)") (class "Default")
      (node (ref "R71") (pin "1") (pinfunction "1_1") (pintype "passive"))
      (node (ref "TRIP8") (pin "2") (pinfunction "POS_2") (pintype "passive"))
    )
    (net (code "56") (name "Net-(TRIP9-NEG)") (class "Default")
      (node (ref "Q5") (pin "D") (pinfunction "D_D") (pintype "passive"))
      (node (ref "TRIP9") (pin "1") (pinfunction "NEG_1") (pintype "passive"))
    )
    (net (code "57") (name "Net-(TRIP9-POS)") (class "Default")
      (node (ref "R72") (pin "1") (pinfunction "1_1") (pintype "passive"))
      (node (ref "TRIP9") (pin "2") (pinfunction "POS_2") (pintype "passive"))
    )
    (net (code "58") (name "Net-(TRIP10-NEG)") (class "Default")
      (node (ref "Q13") (pin "D") (pinfunction "D_D") (pintype "passive"))
      (node (ref "TRIP10") (pin "1") (pinfunction "NEG_1") (pintype "passive"))
    )
    (net (code "59") (name "Net-(TRIP10-POS)") (class "Default")
      (node (ref "R73") (pin "1") (pinfunction "1_1") (pintype "passive"))
      (node (ref "TRIP10") (pin "2") (pinfunction "POS_2") (pintype "passive"))
    )
    (net (code "60") (name "Net-(TRIP11-NEG)") (class "Default")
      (node (ref "Q14") (pin "D") (pinfunction "D_D") (pintype "passive"))
      (node (ref "TRIP11") (pin "1") (pinfunction "NEG_1") (pintype "passive"))
    )
    (net (code "61") (name "Net-(TRIP11-POS)") (class "Default")
      (node (ref "R74") (pin "1") (pinfunction "1_1") (pintype "passive"))
      (node (ref "TRIP11") (pin "2") (pinfunction "POS_2") (pintype "passive"))
    )
    (net (code "62") (name "Net-(TRIP12-NEG)") (class "Default")
      (node (ref "Q6") (pin "D") (pinfunction "D_D") (pintype "passive"))
      (node (ref "TRIP12") (pin "1") (pinfunction "NEG_1") (pintype "passive"))
    )
    (net (code "63") (name "Net-(TRIP12-POS)") (class "Default")
      (node (ref "R75") (pin "1") (pinfunction "1_1") (pintype "passive"))
      (node (ref "TRIP12") (pin "2") (pinfunction "POS_2") (pintype "passive"))
    )
    (net (code "64") (name "Net-(TRIP13-NEG)") (class "Default")
      (node (ref "Q7") (pin "D") (pinfunction "D_D") (pintype "passive"))
      (node (ref "TRIP13") (pin "1") (pinfunction "NEG_1") (pintype "passive"))
    )
    (net (code "65") (name "Net-(TRIP13-POS)") (class "Default")
      (node (ref "R76") (pin "1") (pinfunction "1_1") (pintype "passive"))
      (node (ref "TRIP13") (pin "2") (pinfunction "POS_2") (pintype "passive"))
    )
    (net (code "66") (name "Net-(TRIP14-NEG)") (class "Default")
      (node (ref "Q15") (pin "D") (pinfunction "D_D") (pintype "passive"))
      (node (ref "TRIP14") (pin "1") (pinfunction "NEG_1") (pintype "passive"))
    )
    (net (code "67") (name "Net-(TRIP14-POS)") (class "Default")
      (node (ref "R77") (pin "1") (pinfunction "1_1") (pintype "passive"))
      (node (ref "TRIP14") (pin "2") (pinfunction "POS_2") (pintype "passive"))
    )
    (net (code "68") (name "Net-(TRIP15-NEG)") (class "Default")
      (node (ref "Q16") (pin "D") (pinfunction "D_D") (pintype "passive"))
      (node (ref "TRIP15") (pin "1") (pinfunction "NEG_1") (pintype "passive"))
    )
    (net (code "69") (name "Net-(TRIP15-POS)") (class "Default")
      (node (ref "R78") (pin "1") (pinfunction "1_1") (pintype "passive"))
      (node (ref "TRIP15") (pin "2") (pinfunction "POS_2") (pintype "passive"))
    )
    (net (code "70") (name "Net-(TRIP16-NEG)") (class "Default")
      (node (ref "Q8") (pin "D") (pinfunction "D_D") (pintype "passive"))
      (node (ref "TRIP16") (pin "1") (pinfunction "NEG_1") (pintype "passive"))
    )
    (net (code "71") (name "Net-(TRIP16-POS)") (class "Default")
      (node (ref "R79") (pin "1") (pinfunction "1_1") (pintype "passive"))
      (node (ref "TRIP16") (pin "2") (pinfunction "POS_2") (pintype "passive"))
    )
    (net (code "72") (name "Net-(U15-R1)") (class "Default")
      (node (ref "R100") (pin "2") (pinfunction "2_2") (pintype "passive"))
      (node (ref "SW1") (pin "3") (pinfunction "3_3") (pintype "passive"))
      (node (ref "SW1") (pin "4") (pinfunction "4_4") (pintype "passive"))
      (node (ref "U15") (pin "11") (pinfunction "R3_11") (pintype "passive"))
      (node (ref "U15") (pin "15") (pinfunction "R4_15") (pintype "passive"))
      (node (ref "U15") (pin "3") (pinfunction "R1_3") (pintype "passive"))
      (node (ref "U15") (pin "7") (pinfunction "R2_7") (pintype "passive"))
      (node (ref "U17") (pin "11") (pinfunction "R3_11") (pintype "passive"))
      (node (ref "U17") (pin "15") (pinfunction "R4_15") (pintype "passive"))
      (node (ref "U17") (pin "3") (pinfunction "R1_3") (pintype "passive"))
      (node (ref "U17") (pin "7") (pinfunction "R2_7") (pintype "passive"))
      (node (ref "U18") (pin "11") (pinfunction "R3_11") (pintype "passive"))
      (node (ref "U18") (pin "15") (pinfunction "R4_15") (pintype "passive"))
      (node (ref "U18") (pin "3") (pinfunction "R1_3") (pintype "passive"))
      (node (ref "U18") (pin "7") (pinfunction "R2_7") (pintype "passive"))
      (node (ref "U20") (pin "11") (pinfunction "R3_11") (pintype "passive"))
      (node (ref "U20") (pin "15") (pinfunction "R4_15") (pintype "passive"))
      (node (ref "U20") (pin "3") (pinfunction "R1_3") (pintype "passive"))
      (node (ref "U20") (pin "7") (pinfunction "R2_7") (pintype "passive"))
    )
    (net (code "73") (name "unconnected-(U19-Pad13)") (class "Default")
      (node (ref "U19") (pin "13") (pinfunction "13_13") (pintype "passive"))
    )
  )
)
